# Power.net
KiCad netlist of a schematic drawn in Altium Designer
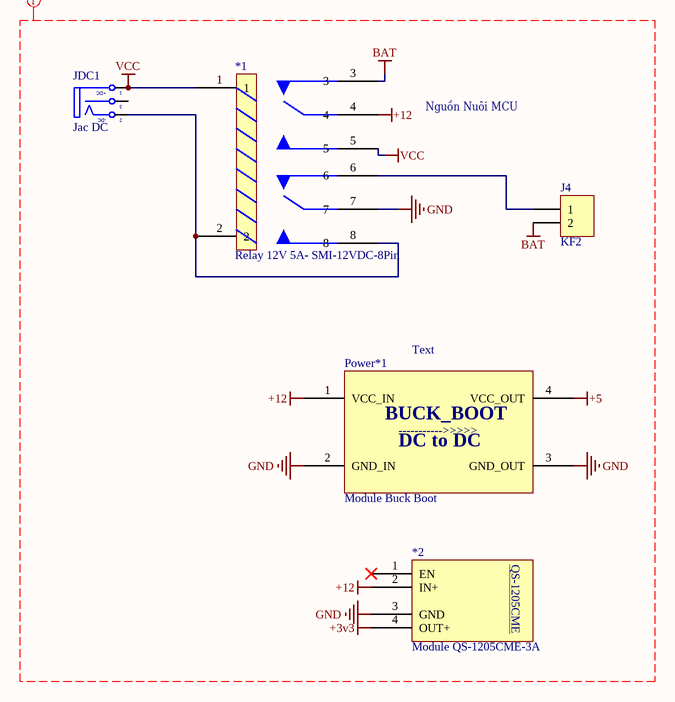
[diagram p0: Power.SchDoc]

(export (version "E")
  (design (tool "Eeschema 10.0.6"))
  (components
    (comp (ref "*1")
      (value "Relay 12V 5A- SMI-12VDC-8Pin")
      (footprint "Relay SMI-12VDC-SL-8Pin")
      (libsource (lib "Diy_Module") (part "Relay 12V 5A- SMI-12VDC-8Pin"))
    )
    (comp (ref "*2")
      (value "Module QS-1205CME-3A")
      (footprint "QS-1205CME-3A")
      (description "Mạch Hạ Áp Mini 3A Nhiều Đầu Ra QS-1205CME-3A")
      (libsource (lib "Diy_Module") (part "Module QS-1205CME-3A"))
    )
    (comp (ref "J4")
      (value "KF2")
      (footprint "KF2-3.5")
      (fields
        (field (name "MANUFACTURER") "Würth Elektronik eiSos GmbH")
        (field (name "PARTNO") "691103110002")
        (field (name "CREATED BY") "Karrer Zheng")
      )
      (libsource (lib "TechMT.VN_Lib_Project v2") (part "KF2"))
    )
    (comp (ref "JDC1")
      (value "Jac DC")
      (footprint "DC-IN")
      (description "Jac DC input")
      (libsource (lib "syhaunguyen") (part "DCIN"))
    )
    (comp (ref "Power*1")
      (value "Module Buck Boot")
      (footprint "Module_BUCK_BOOT")
      (libsource (lib "Diy_Module") (part "Module Buck Boot"))
    )
  )
  (nets
    (net (code "1") (name "+3v3") (class "Default")
      (node (ref "*2") (pin "4") (pinfunction "OUT+_4") (pintype "passive"))
    )
    (net (code "2") (name "+5") (class "Default")
      (node (ref "Power*1") (pin "4") (pinfunction "VCC_OUT_4") (pintype "passive"))
    )
    (net (code "3") (name "+12") (class "Default")
      (node (ref "*1") (pin "4") (pinfunction "4_4") (pintype "passive"))
      (node (ref "*2") (pin "2") (pinfunction "IN+_2") (pintype "passive"))
      (node (ref "Power*1") (pin "1") (pinfunction "VCC_IN_1") (pintype "passive"))
    )
    (net (code "4") (name "BAT") (class "Default")
      (node (ref "*1") (pin "3") (pinfunction "3_3") (pintype "passive"))
      (node (ref "J4") (pin "2") (pinfunction "2_2") (pintype "passive"))
    )
    (net (code "5") (name "GND") (class "Default")
      (node (ref "*1") (pin "7") (pinfunction "7_7") (pintype "passive"))
      (node (ref "*2") (pin "3") (pinfunction "GND_3") (pintype "passive"))
      (node (ref "Power*1") (pin "2") (pinfunction "GND_IN_2") (pintype "passive"))
      (node (ref "Power*1") (pin "3") (pinfunction "GND_OUT_3") (pintype "passive"))
    )
    (net (code "6") (name "Net-(*1-Pad6)") (class "Default")
      (node (ref "*1") (pin "6") (pinfunction "6_6") (pintype "passive"))
      (node (ref "J4") (pin "1") (pinfunction "1_1") (pintype "passive"))
    )
    (net (code "7") (name "Net-(JDC1-TN)") (class "Default")
      (node (ref "*1") (pin "2") (pinfunction "2_2") (pintype "passive"))
      (node (ref "*1") (pin "8") (pinfunction "8_8") (pintype "passive"))
      (node (ref "JDC1") (pin "2") (pinfunction "TN_2") (pintype "passive"))
    )
    (net (code "8") (name "VCC") (class "Default")
      (node (ref "*1") (pin "1") (pinfunction "1_1") (pintype "passive"))
      (node (ref "*1") (pin "5") (pinfunction "5_5") (pintype "passive"))
      (node (ref "JDC1") (pin "1") (pinfunction "T_1") (pintype "passive"))
    )
    (net (code "9") (name "unconnected-(*2-EN-Pad1)") (class "Default")
      (node (ref "*2") (pin "1") (pinfunction "EN_1") (pintype "passive+no_connect"))
    )
    (net (code "10") (name "unconnected-(JDC1-S-Pad3)") (class "Default")
      (node (ref "JDC1") (pin "3") (pinfunction "S_3") (pintype "power_in"))
    )
  )
)
